# PDOC_-_AMS.net
KiCad netlist of a schematic drawn in Altium Designer
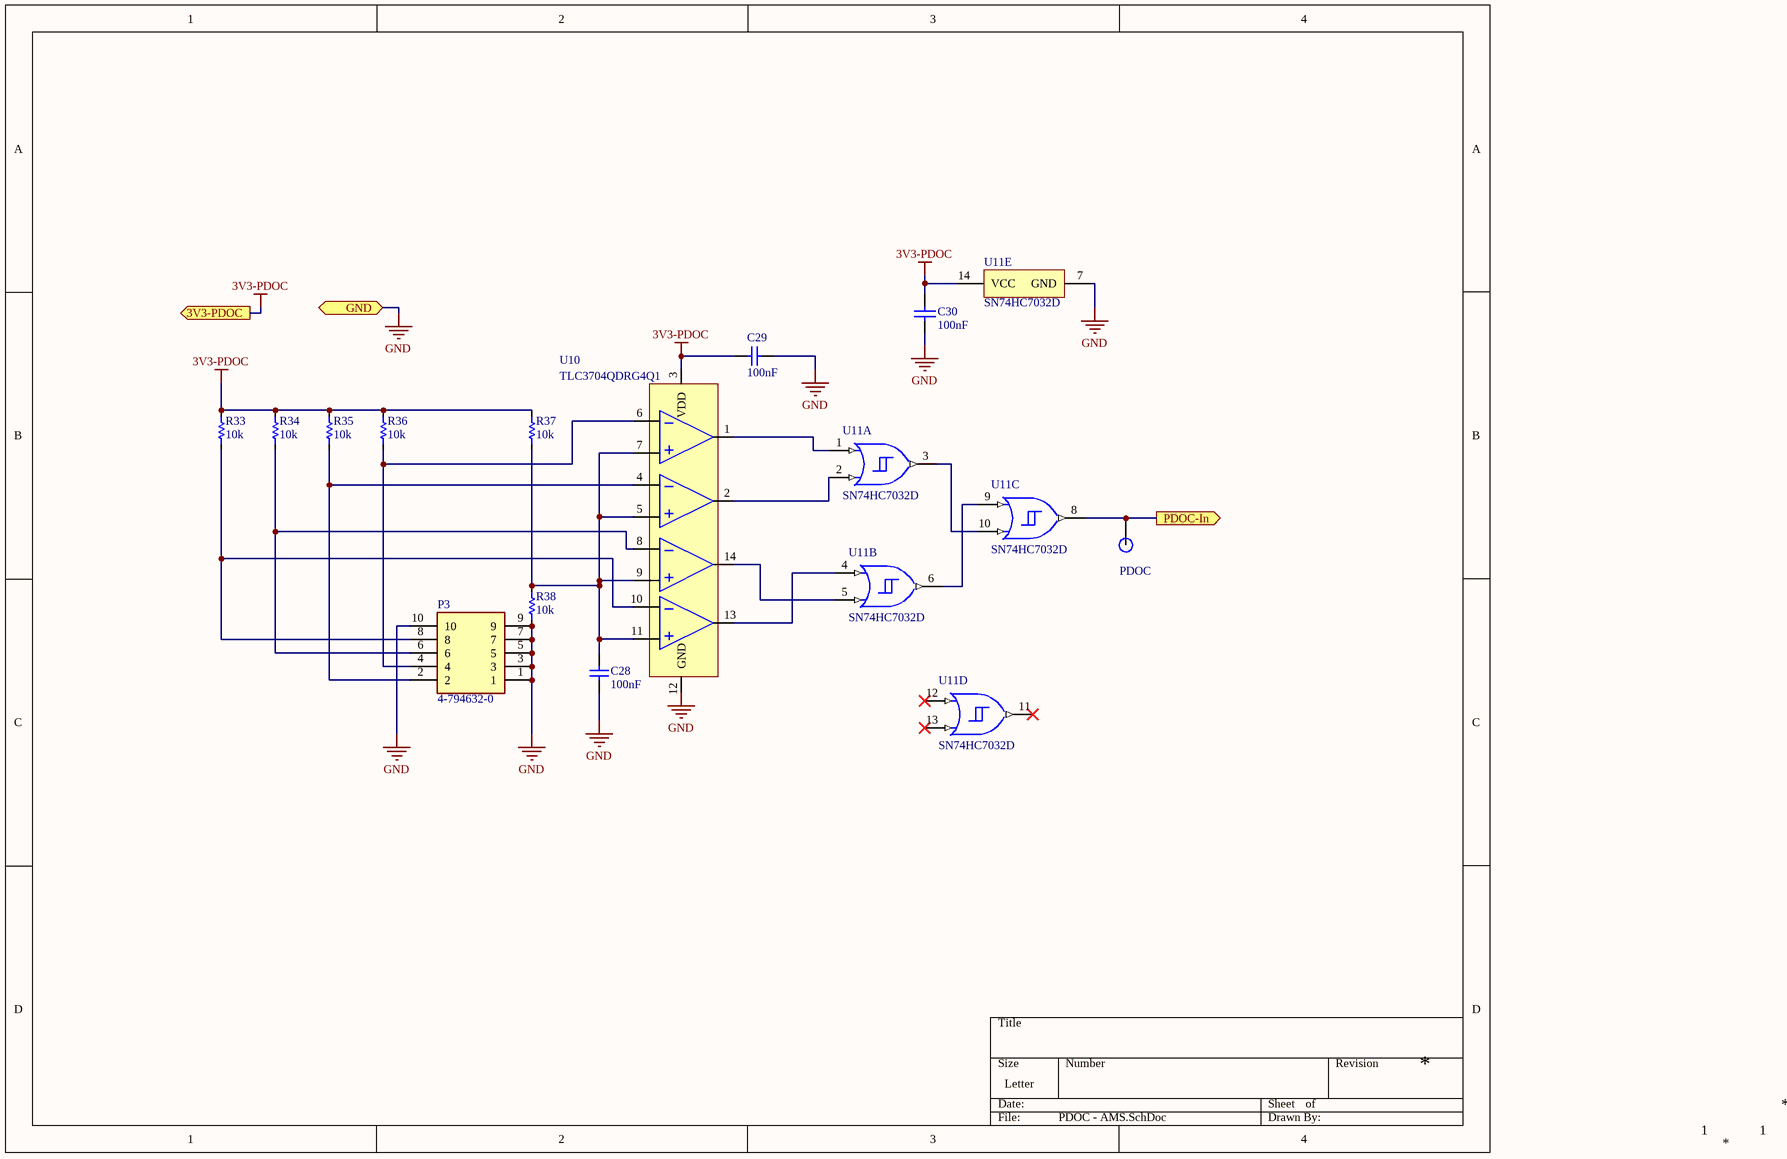
[diagram p0: PDOC - AMS.SchDoc]

(export (version "E")
  (design (tool "Eeschema 10.0.6"))
  (components
    (comp (ref "C28")
      (value "100nF")
      (footprint "C_0603")
      (description "Capacitor")
      (fields (field (name "Comment") "C0603C104K3RAC7013"))
      (libsource (lib "Passives") (part "Capacitor"))
    )
    (comp (ref "C29")
      (value "100nF")
      (footprint "C_0603")
      (description "Capacitor")
      (fields (field (name "Comment") "C0603C104K3RAC7013"))
      (libsource (lib "Passives") (part "Capacitor"))
    )
    (comp (ref "C30")
      (value "100nF")
      (footprint "CAP0603")
      (fields (field (name "Comment") "C0603C104K3RAC7013") (field (name "PUBLISHER") "Altium Limited"))
      (libsource (lib "Miscellaneous Devices") (part "Cap"))
    )
    (comp (ref "P3")
      (value "4-794632-0")
      (footprint "SHDR10W82P300_2X5_1586X686X944P")
      (description "Connector")
      (fields (field (name "MOUSER PART NUMBER") "571-4-794632-0"))
      (libsource (lib "SamacSys") (part "4-794632-0"))
    )
    (comp (ref "PDOC")
      (value "1.2mm Test point")
      (footprint "Test Point")
      (libsource (lib "PCHLib") (part "Test Point"))
    )
    (comp (ref "R33")
      (value "10k")
      (footprint "R-0603")
      (description "Resistor")
      (fields (field (name "Comment") "RC0603FR-1310KL"))
      (libsource (lib "Passives") (part "Resistor"))
    )
    (comp (ref "R34")
      (value "10k")
      (footprint "R-0603")
      (description "Resistor")
      (fields (field (name "Comment") "RC0603FR-1310KL"))
      (libsource (lib "Passives") (part "Resistor"))
    )
    (comp (ref "R35")
      (value "10k")
      (footprint "R-0603")
      (description "Resistor")
      (fields (field (name "Comment") "RC0603FR-1310KL"))
      (libsource (lib "Passives") (part "Resistor"))
    )
    (comp (ref "R36")
      (value "10k")
      (footprint "R-0603")
      (description "Resistor")
      (fields (field (name "Comment") "RC0603FR-1310KL"))
      (libsource (lib "Passives") (part "Resistor"))
    )
    (comp (ref "R37")
      (value "10k")
      (footprint "R-0603")
      (description "Resistor")
      (fields (field (name "Comment") "RC0603FR-1310KL"))
      (libsource (lib "Passives") (part "Resistor"))
    )
    (comp (ref "R38")
      (value "10k")
      (footprint "R-0603")
      (description "Resistor")
      (fields (field (name "Comment") "RC0603FR-1310KL"))
      (libsource (lib "Passives") (part "Resistor"))
    )
    (comp (ref "U10")
      (value "TLC3704QDRG4Q1")
      (footprint "SOIC127P600X175-14N")
      (description "IC VOLT COMPARATOR QUAD 14-SOIC")
      (libsource (lib "Logic") (part "TLC3704QDRG4Q1"))
    )
    (comp (ref "U11")
      (value "SN74HC7032D")
      (footprint "D0014A_L")
      (description "Quadruple Positive-OR Gates With Schmitt-Trigger Inputs, D0014A, TUBE")
      (fields
        (field (name "GENERIC PART NUMBER") "SN74HC7032")
        (field (name "MANUFACTURER") "Texas Instruments")
      )
      (libsource (lib "Altium Content Vault") (part "TI-SN74HC7032-D0014A-14"))
    )
  )
  (nets
    (net (code "2") (name "/PDOC-In") (class "Default")
      (node (ref "PDOC") (pin "1") (pinfunction "1_1") (pintype "passive"))
      (node (ref "U11") (pin "8") (pinfunction "3Y_8") (pintype "output"))
    )
    (net (code "3") (name "3V3-PDOC") (class "Default")
      (node (ref "C29") (pin "2") (pinfunction "2_2") (pintype "passive"))
      (node (ref "C30") (pin "2") (pinfunction "2_2") (pintype "passive"))
      (node (ref "R33") (pin "2") (pinfunction "2_2") (pintype "passive"))
      (node (ref "R34") (pin "2") (pinfunction "2_2") (pintype "passive"))
      (node (ref "R35") (pin "2") (pinfunction "2_2") (pintype "passive"))
      (node (ref "R36") (pin "2") (pinfunction "2_2") (pintype "passive"))
      (node (ref "R37") (pin "2") (pinfunction "2_2") (pintype "passive"))
      (node (ref "U10") (pin "3") (pinfunction "VDD_3") (pintype "passive"))
      (node (ref "U11") (pin "14") (pinfunction "VCC_14") (pintype "power_in"))
    )
    (net (code "4") (name "GND") (class "Default")
      (node (ref "C28") (pin "1") (pinfunction "1_1") (pintype "passive"))
      (node (ref "C29") (pin "1") (pinfunction "1_1") (pintype "passive"))
      (node (ref "C30") (pin "1") (pinfunction "1_1") (pintype "passive"))
      (node (ref "P3") (pin "1") (pinfunction "1_1") (pintype "passive"))
      (node (ref "P3") (pin "10") (pinfunction "10_10") (pintype "passive"))
      (node (ref "P3") (pin "3") (pinfunction "3_3") (pintype "passive"))
      (node (ref "P3") (pin "5") (pinfunction "5_5") (pintype "passive"))
      (node (ref "P3") (pin "7") (pinfunction "7_7") (pintype "passive"))
      (node (ref "P3") (pin "9") (pinfunction "9_9") (pintype "passive"))
      (node (ref "R38") (pin "1") (pinfunction "1_1") (pintype "passive"))
      (node (ref "U10") (pin "12") (pinfunction "GND_12") (pintype "passive"))
      (node (ref "U11") (pin "7") (pinfunction "GND_7") (pintype "power_in"))
    )
    (net (code "5") (name "Net-(U10-In1+)") (class "Default")
      (node (ref "C28") (pin "2") (pinfunction "2_2") (pintype "passive"))
      (node (ref "R37") (pin "1") (pinfunction "1_1") (pintype "passive"))
      (node (ref "R38") (pin "2") (pinfunction "2_2") (pintype "passive"))
      (node (ref "U10") (pin "11") (pinfunction "In4+_11") (pintype "passive"))
      (node (ref "U10") (pin "5") (pinfunction "In2+_5") (pintype "passive"))
      (node (ref "U10") (pin "7") (pinfunction "In1+_7") (pintype "passive"))
      (node (ref "U10") (pin "9") (pinfunction "In3+_9") (pintype "passive"))
    )
    (net (code "6") (name "Net-(U10-In1-)") (class "Default")
      (node (ref "P3") (pin "4") (pinfunction "4_4") (pintype "passive"))
      (node (ref "R36") (pin "1") (pinfunction "1_1") (pintype "passive"))
      (node (ref "U10") (pin "6") (pinfunction "In1-_6") (pintype "passive"))
    )
    (net (code "7") (name "Net-(U10-In2-)") (class "Default")
      (node (ref "P3") (pin "2") (pinfunction "2_2") (pintype "passive"))
      (node (ref "R35") (pin "1") (pinfunction "1_1") (pintype "passive"))
      (node (ref "U10") (pin "4") (pinfunction "In2-_4") (pintype "passive"))
    )
    (net (code "8") (name "Net-(U10-In3-)") (class "Default")
      (node (ref "P3") (pin "6") (pinfunction "6_6") (pintype "passive"))
      (node (ref "R34") (pin "1") (pinfunction "1_1") (pintype "passive"))
      (node (ref "U10") (pin "8") (pinfunction "In3-_8") (pintype "passive"))
    )
    (net (code "9") (name "Net-(U10-In4-)") (class "Default")
      (node (ref "P3") (pin "8") (pinfunction "8_8") (pintype "passive"))
      (node (ref "R33") (pin "1") (pinfunction "1_1") (pintype "passive"))
      (node (ref "U10") (pin "10") (pinfunction "In4-_10") (pintype "passive"))
    )
    (net (code "10") (name "Net-(U10-Out1)") (class "Default")
      (node (ref "U10") (pin "1") (pinfunction "Out1_1") (pintype "passive"))
      (node (ref "U11") (pin "1") (pinfunction "1A_1") (pintype "input"))
    )
    (net (code "11") (name "Net-(U10-Out2)") (class "Default")
      (node (ref "U10") (pin "2") (pinfunction "Out2_2") (pintype "passive"))
      (node (ref "U11") (pin "2") (pinfunction "1B_2") (pintype "input"))
    )
    (net (code "12") (name "Net-(U10-Out3)") (class "Default")
      (node (ref "U10") (pin "14") (pinfunction "Out3_14") (pintype "passive"))
      (node (ref "U11") (pin "5") (pinfunction "2B_5") (pintype "input"))
    )
    (net (code "13") (name "Net-(U10-Out4)") (class "Default")
      (node (ref "U10") (pin "13") (pinfunction "Out4_13") (pintype "passive"))
      (node (ref "U11") (pin "4") (pinfunction "2A_4") (pintype "input"))
    )
    (net (code "14") (name "Net-(U11A-1Y)") (class "Default")
      (node (ref "U11") (pin "10") (pinfunction "3B_10") (pintype "input"))
      (node (ref "U11") (pin "3") (pinfunction "1Y_3") (pintype "output"))
    )
    (net (code "15") (name "Net-(U11B-2Y)") (class "Default")
      (node (ref "U11") (pin "6") (pinfunction "2Y_6") (pintype "output"))
      (node (ref "U11") (pin "9") (pinfunction "3A_9") (pintype "input"))
    )
    (net (code "16") (name "unconnected-(U11D-4A-Pad12)") (class "Default")
      (node (ref "U11") (pin "12") (pinfunction "4A_12") (pintype "input+no_connect"))
    )
    (net (code "17") (name "unconnected-(U11D-4B-Pad13)") (class "Default")
      (node (ref "U11") (pin "13") (pinfunction "4B_13") (pintype "input+no_connect"))
    )
    (net (code "18") (name "unconnected-(U11D-4Y-Pad11)") (class "Default")
      (node (ref "U11") (pin "11") (pinfunction "4Y_11") (pintype "output+no_connect"))
    )
  )
)
